# AD_5689_DAC.net
KiCad netlist of a schematic drawn in Altium Designer
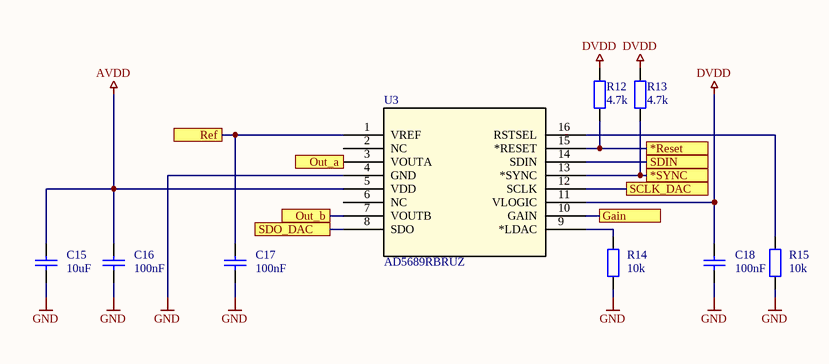
[diagram p0: AD_5689_DAC.SchDoc]

(export (version "E")
  (design (tool "Eeschema 10.0.6"))
  (components
    (comp (ref "C15")
      (value "10uF")
      (footprint "C1206-KUE")
      (description "Capacitor")
      (fields (field (name "MANUFACTURER") "Kemet") (field (name "PUBLISHER") "Altium Limited"))
      (libsource (lib "ExtrapartsKUE_V01") (part "Capacitor"))
    )
    (comp (ref "C16")
      (value "100nF")
      (footprint "C1206-KUE")
      (description "Capacitor")
      (fields (field (name "MANUFACTURER") "Kemet") (field (name "PUBLISHER") "Altium Limited"))
      (libsource (lib "ExtrapartsKUE_V01") (part "Capacitor"))
    )
    (comp (ref "C17")
      (value "100nF")
      (footprint "C1206-KUE")
      (description "Capacitor")
      (fields (field (name "MANUFACTURER") "Kemet") (field (name "PUBLISHER") "Altium Limited"))
      (libsource (lib "ExtrapartsKUE_V01") (part "Capacitor"))
    )
    (comp (ref "C18")
      (value "100nF")
      (footprint "C1206-KUE")
      (description "Capacitor")
      (fields (field (name "MANUFACTURER") "Kemet") (field (name "PUBLISHER") "Altium Limited"))
      (libsource (lib "ExtrapartsKUE_V01") (part "Capacitor"))
    )
    (comp (ref "R12")
      (value "4.7k")
      (footprint "C1206-KUE")
      (description "Resistor SMD")
      (fields (field (name "MANUFACTURER") "AVX") (field (name "PUBLISHER") "Altium Limited"))
      (libsource (lib "ExtrapartsKUE_V01") (part "ResistorSMD"))
    )
    (comp (ref "R13")
      (value "4.7k")
      (footprint "C1206-KUE")
      (description "Resistor SMD")
      (fields (field (name "MANUFACTURER") "AVX") (field (name "PUBLISHER") "Altium Limited"))
      (libsource (lib "ExtrapartsKUE_V01") (part "ResistorSMD"))
    )
    (comp (ref "R14")
      (value "10k")
      (footprint "C1206-KUE")
      (description "Resistor SMD")
      (fields (field (name "MANUFACTURER") "AVX") (field (name "PUBLISHER") "Altium Limited"))
      (libsource (lib "ExtrapartsKUE_V01") (part "ResistorSMD"))
    )
    (comp (ref "R15")
      (value "10k")
      (footprint "C1206-KUE")
      (description "Resistor SMD")
      (fields (field (name "MANUFACTURER") "AVX") (field (name "PUBLISHER") "Altium Limited"))
      (libsource (lib "ExtrapartsKUE_V01") (part "ResistorSMD"))
    )
    (comp (ref "U3")
      (value "AD5689RBRUZ")
      (footprint "RU_16_ADI")
      (description "Dual, 16-Bit nanoDAC+ with 2 ppm/Â°C Reference, SPI Interface")
      (fields (field (name "COPYRIGHT") "Copyright (C) 2026 Ultra Librarian. All rights reserved."))
      (libsource (lib "MyOwnParts") (part "AD5689RBRUZ"))
    )
  )
  (nets
    (net (code "1") (name "/*Reset") (class "Default")
      (node (ref "R12") (pin "2") (pinfunction "2_2") (pintype "passive"))
      (node (ref "U3") (pin "15") (pinfunction "*RESET_15") (pintype "passive"))
    )
    (net (code "2") (name "/*SYNC") (class "Default")
      (node (ref "R13") (pin "2") (pinfunction "2_2") (pintype "passive"))
      (node (ref "U3") (pin "13") (pinfunction "*SYNC_13") (pintype "passive"))
    )
    (net (code "3") (name "/Gain") (class "Default")
      (node (ref "U3") (pin "10") (pinfunction "GAIN_10") (pintype "passive"))
    )
    (net (code "4") (name "/Out_a") (class "Default")
      (node (ref "U3") (pin "3") (pinfunction "VOUTA_3") (pintype "passive"))
    )
    (net (code "5") (name "/Out_b") (class "Default")
      (node (ref "U3") (pin "7") (pinfunction "VOUTB_7") (pintype "passive"))
    )
    (net (code "6") (name "/Ref") (class "Default")
      (node (ref "C17") (pin "2") (pinfunction "2_2") (pintype "passive"))
      (node (ref "U3") (pin "1") (pinfunction "VREF_1") (pintype "power_in"))
    )
    (net (code "7") (name "/SCLK_DAC") (class "Default")
      (node (ref "U3") (pin "12") (pinfunction "SCLK_12") (pintype "passive"))
    )
    (net (code "8") (name "/SDIN") (class "Default")
      (node (ref "U3") (pin "14") (pinfunction "SDIN_14") (pintype "passive"))
    )
    (net (code "9") (name "/SDO_DAC") (class "Default")
      (node (ref "U3") (pin "8") (pinfunction "SDO_8") (pintype "passive"))
    )
    (net (code "10") (name "AVDD") (class "Default")
      (node (ref "C15") (pin "2") (pinfunction "2_2") (pintype "passive"))
      (node (ref "C16") (pin "2") (pinfunction "2_2") (pintype "passive"))
      (node (ref "U3") (pin "5") (pinfunction "VDD_5") (pintype "power_in"))
    )
    (net (code "11") (name "DVDD") (class "Default")
      (node (ref "C18") (pin "2") (pinfunction "2_2") (pintype "passive"))
      (node (ref "R12") (pin "1") (pinfunction "1_1") (pintype "passive"))
      (node (ref "R13") (pin "1") (pinfunction "1_1") (pintype "passive"))
      (node (ref "U3") (pin "11") (pinfunction "VLOGIC_11") (pintype "power_in"))
    )
    (net (code "12") (name "GND") (class "Default")
      (node (ref "C15") (pin "1") (pinfunction "1_1") (pintype "passive"))
      (node (ref "C16") (pin "1") (pinfunction "1_1") (pintype "passive"))
      (node (ref "C17") (pin "1") (pinfunction "1_1") (pintype "passive"))
      (node (ref "C18") (pin "1") (pinfunction "1_1") (pintype "passive"))
      (node (ref "R14") (pin "2") (pinfunction "2_2") (pintype "passive"))
      (node (ref "R15") (pin "2") (pinfunction "2_2") (pintype "passive"))
      (node (ref "U3") (pin "4") (pinfunction "GND_4") (pintype "power_in"))
    )
    (net (code "13") (name "Net-(U3-*LDAC)") (class "Default")
      (node (ref "R14") (pin "1") (pinfunction "1_1") (pintype "passive"))
      (node (ref "U3") (pin "9") (pinfunction "*LDAC_9") (pintype "passive"))
    )
    (net (code "14") (name "Net-(U3-RSTSEL)") (class "Default")
      (node (ref "R15") (pin "1") (pinfunction "1_1") (pintype "passive"))
      (node (ref "U3") (pin "16") (pinfunction "RSTSEL_16") (pintype "power_in"))
    )
    (net (code "15") (name "unconnected-(U3-NC-Pad2)") (class "Default")
      (node (ref "U3") (pin "2") (pinfunction "NC_2") (pintype "passive"))
    )
    (net (code "16") (name "unconnected-(U3-NC-Pad6)") (class "Default")
      (node (ref "U3") (pin "6") (pinfunction "NC_6") (pintype "passive"))
    )
  )
)
